# Sheet1.net
KiCad netlist of a schematic drawn in Altium Designer
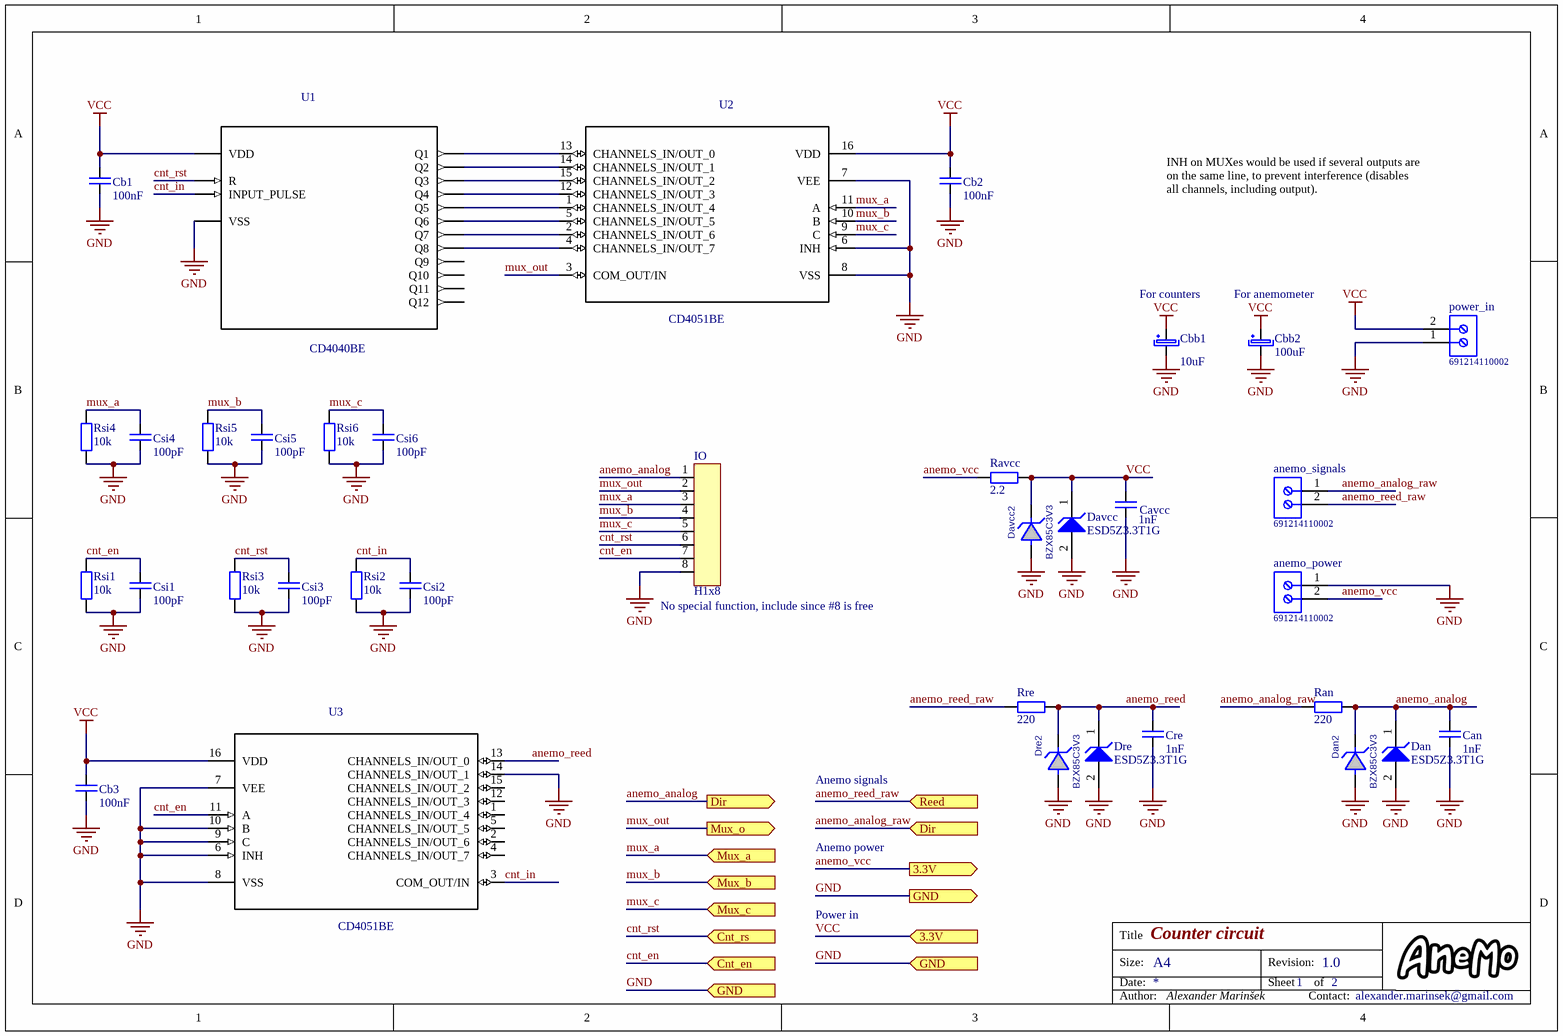
[diagram p0: Sheet1.SchDoc]

(export (version "E")
  (design (tool "Eeschema 10.0.6"))
  (components
    (comp (ref "anemo_power")
      (value "691214110002")
      (footprint "691214110002")
      (description "Serie 2141 - 3.50 mm Horizontal Entry Modular with Rising Cage Clamp WR-TBL, 2 pin")
      (fields (field (name "PUBLISHER") "Wurth Elektronik"))
      (libsource (lib "Altium_TBL_RISING_CAGE_SYSTEM (rev18b)") (part "691214110002"))
    )
    (comp (ref "anemo_signals")
      (value "691214110002")
      (footprint "691214110002")
      (description "Serie 2141 - 3.50 mm Horizontal Entry Modular with Rising Cage Clamp WR-TBL, 2 pin")
      (fields (field (name "PUBLISHER") "Wurth Elektronik"))
      (libsource (lib "Altium_TBL_RISING_CAGE_SYSTEM (rev18b)") (part "691214110002"))
    )
    (comp (ref "Can")
      (value "1nF")
      (footprint "C0805(2012)_M")
      (description "Capacitor")
      (libsource (lib "General") (part "C"))
    )
    (comp (ref "Cavcc")
      (value "1nF")
      (footprint "C0805(2012)_M")
      (description "Capacitor")
      (libsource (lib "General") (part "C"))
    )
    (comp (ref "Cb1")
      (value "100nF")
      (footprint "C0805(2012)_M")
      (description "Capacitor")
      (libsource (lib "General") (part "C"))
    )
    (comp (ref "Cb2")
      (value "100nF")
      (footprint "C0805(2012)_M")
      (description "Capacitor")
      (libsource (lib "General") (part "C"))
    )
    (comp (ref "Cb3")
      (value "100nF")
      (footprint "C0805(2012)_M")
      (description "Capacitor")
      (libsource (lib "General") (part "C"))
    )
    (comp (ref "Cbb1")
      (value "10uF")
      (footprint "C-SMD-ELKO-D")
      (description "Capacitor Polarized")
      (libsource (lib "General") (part "C+"))
    )
    (comp (ref "Cbb2")
      (value "100uF")
      (footprint "C-SMD-ELKO-D")
      (description "Capacitor Polarized")
      (libsource (lib "General") (part "C+"))
    )
    (comp (ref "Cre")
      (value "1nF")
      (footprint "C0805(2012)_M")
      (description "Capacitor")
      (libsource (lib "General") (part "C"))
    )
    (comp (ref "Csi1")
      (value "100pF")
      (footprint "C0805(2012)_M")
      (description "Capacitor")
      (libsource (lib "General") (part "C"))
    )
    (comp (ref "Csi2")
      (value "100pF")
      (footprint "C0805(2012)_M")
      (description "Capacitor")
      (libsource (lib "General") (part "C"))
    )
    (comp (ref "Csi3")
      (value "100pF")
      (footprint "C0805(2012)_M")
      (description "Capacitor")
      (libsource (lib "General") (part "C"))
    )
    (comp (ref "Csi4")
      (value "100pF")
      (footprint "C0805(2012)_M")
      (description "Capacitor")
      (libsource (lib "General") (part "C"))
    )
    (comp (ref "Csi5")
      (value "100pF")
      (footprint "C0805(2012)_M")
      (description "Capacitor")
      (libsource (lib "General") (part "C"))
    )
    (comp (ref "Csi6")
      (value "100pF")
      (footprint "C0805(2012)_M")
      (description "Capacitor")
      (libsource (lib "General") (part "C"))
    )
    (comp (ref "Dan")
      (value "ESD5Z3.3T1G")
      (footprint "ONSC-SOD-523-2-502-01_V")
      (fields (field (name "MANUFACTURER") "On Semiconductor"))
      (libsource (lib "ON Semi ESD Protection Diodes & Arrays") (part "ESD5Z3.3T1G"))
    )
    (comp (ref "Dan2")
      (value "BZX85C3V3")
      (footprint "DO 35 (300MILS)")
      (libsource (lib "SemiCond") (part "BZX85C3V3"))
    )
    (comp (ref "Davcc")
      (value "ESD5Z3.3T1G")
      (footprint "ONSC-SOD-523-2-502-01_V")
      (fields (field (name "MANUFACTURER") "On Semiconductor"))
      (libsource (lib "ON Semi ESD Protection Diodes & Arrays") (part "ESD5Z3.3T1G"))
    )
    (comp (ref "Davcc2")
      (value "BZX85C3V3")
      (footprint "DO 35 (300MILS)")
      (libsource (lib "SemiCond") (part "BZX85C3V3"))
    )
    (comp (ref "Dre")
      (value "ESD5Z3.3T1G")
      (footprint "ONSC-SOD-523-2-502-01_V")
      (fields (field (name "MANUFACTURER") "On Semiconductor"))
      (libsource (lib "ON Semi ESD Protection Diodes & Arrays") (part "ESD5Z3.3T1G"))
    )
    (comp (ref "Dre2")
      (value "BZX85C3V3")
      (footprint "DO 35 (300MILS)")
      (libsource (lib "SemiCond") (part "BZX85C3V3"))
    )
    (comp (ref "IO")
      (value "H1x8")
      (footprint "H1x8")
      (description "Header 1x8 (male)")
      (libsource (lib "Kon_Tipk") (part "H1x8"))
    )
    (comp (ref "power_in")
      (value "691214110002")
      (footprint "691214110002")
      (description "Serie 2141 - 3.50 mm Horizontal Entry Modular with Rising Cage Clamp WR-TBL, 2 pin")
      (fields (field (name "PUBLISHER") "Wurth Elektronik"))
      (libsource (lib "Altium_TBL_RISING_CAGE_SYSTEM (rev18b)") (part "691214110002"))
    )
    (comp (ref "Ran")
      (value "220")
      (footprint "R0805(2012)_M")
      (description "R")
      (libsource (lib "General") (part "R"))
    )
    (comp (ref "Ravcc")
      (value "2.2")
      (footprint "R0805(2012)_M")
      (description "R")
      (libsource (lib "General") (part "R"))
    )
    (comp (ref "Rre")
      (value "220")
      (footprint "R0805(2012)_M")
      (description "R")
      (libsource (lib "General") (part "R"))
    )
    (comp (ref "Rsi1")
      (value "10k")
      (footprint "R0805(2012)_M")
      (description "R")
      (libsource (lib "General") (part "R"))
    )
    (comp (ref "Rsi2")
      (value "10k")
      (footprint "R0805(2012)_M")
      (description "R")
      (libsource (lib "General") (part "R"))
    )
    (comp (ref "Rsi3")
      (value "10k")
      (footprint "R0805(2012)_M")
      (description "R")
      (libsource (lib "General") (part "R"))
    )
    (comp (ref "Rsi4")
      (value "10k")
      (footprint "R0805(2012)_M")
      (description "R")
      (libsource (lib "General") (part "R"))
    )
    (comp (ref "Rsi5")
      (value "10k")
      (footprint "R0805(2012)_M")
      (description "R")
      (libsource (lib "General") (part "R"))
    )
    (comp (ref "Rsi6")
      (value "10k")
      (footprint "R0805(2012)_M")
      (description "R")
      (libsource (lib "General") (part "R"))
    )
    (comp (ref "U1")
      (value "CD4040BE")
      (footprint "*SOIC16")
      (description "Ic Counter Ripple Binary 12 Stage 16dil-300")
      (fields (field (name "MF") "Texas Instruments"))
      (libsource (lib "cd4040") (part "CD4040BE"))
    )
    (comp (ref "U2")
      (value "CD4051BE")
      (footprint "*SOIC16")
      (description "i/c Analg Mx/Dmx 8chan 4051_p_")
      (fields (field (name "MF") "Texas Instruments"))
      (libsource (lib "cd4051") (part "CD4051BE"))
    )
    (comp (ref "U3")
      (value "CD4051BE")
      (footprint "*SOIC16")
      (description "i/c Analg Mx/Dmx 8chan 4051_p_")
      (fields (field (name "MF") "Texas Instruments"))
      (libsource (lib "cd4051") (part "CD4051BE"))
    )
  )
  (nets
    (net (code "1") (name "/anemo_analog") (class "Default")
      (node (ref "Can") (pin "1") (pinfunction "1_1") (pintype "passive"))
      (node (ref "Dan") (pin "1") (pinfunction "K_1") (pintype "passive"))
      (node (ref "Dan2") (pin "K") (pintype "passive"))
      (node (ref "IO") (pin "1") (pinfunction "1_1") (pintype "passive"))
      (node (ref "Ran") (pin "1") (pintype "passive"))
      (node (ref "Ran") (pin "2") (pintype "passive"))
      (node (ref "anemo_signals") (pin "1") (pinfunction "1_1") (pintype "passive"))
    )
    (net (code "2") (name "/anemo_reed") (class "Default")
      (node (ref "Cre") (pin "1") (pinfunction "1_1") (pintype "passive"))
      (node (ref "Dre") (pin "1") (pinfunction "K_1") (pintype "passive"))
      (node (ref "Dre2") (pin "K") (pintype "passive"))
      (node (ref "Rre") (pin "2") (pintype "passive"))
      (node (ref "U3") (pin "13") (pinfunction "CHANNELS_IN/OUT_0_13") (pintype "bidirectional"))
    )
    (net (code "3") (name "/anemo_reed_raw") (class "Default")
      (node (ref "Rre") (pin "1") (pintype "passive"))
      (node (ref "anemo_signals") (pin "2") (pinfunction "2_2") (pintype "passive"))
    )
    (net (code "4") (name "/cnt_en") (class "Default")
      (node (ref "Csi1") (pin "1") (pinfunction "1_1") (pintype "passive"))
      (node (ref "IO") (pin "7") (pinfunction "7_7") (pintype "passive"))
      (node (ref "Rsi1") (pin "1") (pintype "passive"))
      (node (ref "U3") (pin "11") (pinfunction "A_11") (pintype "input"))
    )
    (net (code "5") (name "/cnt_in") (class "Default")
      (node (ref "Csi2") (pin "1") (pinfunction "1_1") (pintype "passive"))
      (node (ref "Rsi2") (pin "1") (pintype "passive"))
      (node (ref "U1") (pin "10") (pinfunction "INPUT_PULSE_10") (pintype "input"))
      (node (ref "U3") (pin "3") (pinfunction "COM_OUT/IN_3") (pintype "bidirectional"))
    )
    (net (code "6") (name "/cnt_rst") (class "Default")
      (node (ref "Csi3") (pin "1") (pinfunction "1_1") (pintype "passive"))
      (node (ref "IO") (pin "6") (pinfunction "6_6") (pintype "passive"))
      (node (ref "Rsi3") (pin "1") (pintype "passive"))
      (node (ref "U1") (pin "11") (pinfunction "R_11") (pintype "input"))
    )
    (net (code "7") (name "/mux_a") (class "Default")
      (node (ref "Csi4") (pin "1") (pinfunction "1_1") (pintype "passive"))
      (node (ref "IO") (pin "3") (pinfunction "3_3") (pintype "passive"))
      (node (ref "Rsi4") (pin "1") (pintype "passive"))
      (node (ref "U2") (pin "11") (pinfunction "A_11") (pintype "input"))
    )
    (net (code "8") (name "/mux_b") (class "Default")
      (node (ref "Csi5") (pin "1") (pinfunction "1_1") (pintype "passive"))
      (node (ref "IO") (pin "4") (pinfunction "4_4") (pintype "passive"))
      (node (ref "Rsi5") (pin "1") (pintype "passive"))
      (node (ref "U2") (pin "10") (pinfunction "B_10") (pintype "input"))
    )
    (net (code "9") (name "/mux_c") (class "Default")
      (node (ref "Csi6") (pin "1") (pinfunction "1_1") (pintype "passive"))
      (node (ref "IO") (pin "5") (pinfunction "5_5") (pintype "passive"))
      (node (ref "Rsi6") (pin "1") (pintype "passive"))
      (node (ref "U2") (pin "9") (pinfunction "C_9") (pintype "input"))
    )
    (net (code "10") (name "/mux_out") (class "Default")
      (node (ref "IO") (pin "2") (pinfunction "2_2") (pintype "passive"))
      (node (ref "U2") (pin "3") (pinfunction "COM_OUT/IN_3") (pintype "bidirectional"))
    )
    (net (code "11") (name "GND") (class "Default")
      (node (ref "Can") (pin "2") (pinfunction "2_2") (pintype "passive"))
      (node (ref "Cavcc") (pin "2") (pinfunction "2_2") (pintype "passive"))
      (node (ref "Cb1") (pin "2") (pinfunction "2_2") (pintype "passive"))
      (node (ref "Cb2") (pin "2") (pinfunction "2_2") (pintype "passive"))
      (node (ref "Cb3") (pin "2") (pinfunction "2_2") (pintype "passive"))
      (node (ref "Cbb1") (pin "2") (pinfunction "2_2") (pintype "passive"))
      (node (ref "Cbb2") (pin "2") (pinfunction "2_2") (pintype "passive"))
      (node (ref "Cre") (pin "2") (pinfunction "2_2") (pintype "passive"))
      (node (ref "Csi1") (pin "2") (pinfunction "2_2") (pintype "passive"))
      (node (ref "Csi2") (pin "2") (pinfunction "2_2") (pintype "passive"))
      (node (ref "Csi3") (pin "2") (pinfunction "2_2") (pintype "passive"))
      (node (ref "Csi4") (pin "2") (pinfunction "2_2") (pintype "passive"))
      (node (ref "Csi5") (pin "2") (pinfunction "2_2") (pintype "passive"))
      (node (ref "Csi6") (pin "2") (pinfunction "2_2") (pintype "passive"))
      (node (ref "Dan") (pin "2") (pinfunction "A_2") (pintype "passive"))
      (node (ref "Dan2") (pin "A") (pintype "passive"))
      (node (ref "Davcc") (pin "2") (pinfunction "A_2") (pintype "passive"))
      (node (ref "Davcc2") (pin "A") (pintype "passive"))
      (node (ref "Dre") (pin "2") (pinfunction "A_2") (pintype "passive"))
      (node (ref "Dre2") (pin "A") (pintype "passive"))
      (node (ref "IO") (pin "8") (pinfunction "8_8") (pintype "passive"))
      (node (ref "Rsi1") (pin "2") (pintype "passive"))
      (node (ref "Rsi2") (pin "2") (pintype "passive"))
      (node (ref "Rsi3") (pin "2") (pintype "passive"))
      (node (ref "Rsi4") (pin "2") (pintype "passive"))
      (node (ref "Rsi5") (pin "2") (pintype "passive"))
      (node (ref "Rsi6") (pin "2") (pintype "passive"))
      (node (ref "U1") (pin "8") (pinfunction "VSS_8") (pintype "passive"))
      (node (ref "U2") (pin "6") (pinfunction "INH_6") (pintype "input"))
      (node (ref "U2") (pin "7") (pinfunction "VEE_7") (pintype "power_in"))
      (node (ref "U2") (pin "8") (pinfunction "VSS_8") (pintype "power_in"))
      (node (ref "U3") (pin "10") (pinfunction "B_10") (pintype "input"))
      (node (ref "U3") (pin "14") (pinfunction "CHANNELS_IN/OUT_1_14") (pintype "bidirectional"))
      (node (ref "U3") (pin "6") (pinfunction "INH_6") (pintype "input"))
      (node (ref "U3") (pin "7") (pinfunction "VEE_7") (pintype "power_in"))
      (node (ref "U3") (pin "8") (pinfunction "VSS_8") (pintype "power_in"))
      (node (ref "U3") (pin "9") (pinfunction "C_9") (pintype "input"))
      (node (ref "anemo_power") (pin "1") (pinfunction "1_1") (pintype "passive"))
      (node (ref "power_in") (pin "1") (pinfunction "1_1") (pintype "passive"))
    )
    (net (code "12") (name "Net-(U1-Q1)") (class "Default")
      (node (ref "U1") (pin "9") (pinfunction "Q1_9") (pintype "output"))
      (node (ref "U2") (pin "13") (pinfunction "CHANNELS_IN/OUT_0_13") (pintype "bidirectional"))
    )
    (net (code "13") (name "Net-(U1-Q2)") (class "Default")
      (node (ref "U1") (pin "7") (pinfunction "Q2_7") (pintype "output"))
      (node (ref "U2") (pin "14") (pinfunction "CHANNELS_IN/OUT_1_14") (pintype "bidirectional"))
    )
    (net (code "14") (name "Net-(U1-Q3)") (class "Default")
      (node (ref "U1") (pin "6") (pinfunction "Q3_6") (pintype "output"))
      (node (ref "U2") (pin "15") (pinfunction "CHANNELS_IN/OUT_2_15") (pintype "bidirectional"))
    )
    (net (code "15") (name "Net-(U1-Q4)") (class "Default")
      (node (ref "U1") (pin "5") (pinfunction "Q4_5") (pintype "output"))
      (node (ref "U2") (pin "12") (pinfunction "CHANNELS_IN/OUT_3_12") (pintype "bidirectional"))
    )
    (net (code "16") (name "Net-(U1-Q5)") (class "Default")
      (node (ref "U1") (pin "3") (pinfunction "Q5_3") (pintype "output"))
      (node (ref "U2") (pin "1") (pinfunction "CHANNELS_IN/OUT_4_1") (pintype "bidirectional"))
    )
    (net (code "17") (name "Net-(U1-Q6)") (class "Default")
      (node (ref "U1") (pin "2") (pinfunction "Q6_2") (pintype "output"))
      (node (ref "U2") (pin "5") (pinfunction "CHANNELS_IN/OUT_5_5") (pintype "bidirectional"))
    )
    (net (code "18") (name "Net-(U1-Q7)") (class "Default")
      (node (ref "U1") (pin "4") (pinfunction "Q7_4") (pintype "output"))
      (node (ref "U2") (pin "2") (pinfunction "CHANNELS_IN/OUT_6_2") (pintype "bidirectional"))
    )
    (net (code "19") (name "Net-(U1-Q8)") (class "Default")
      (node (ref "U1") (pin "13") (pinfunction "Q8_13") (pintype "output"))
      (node (ref "U2") (pin "4") (pinfunction "CHANNELS_IN/OUT_7_4") (pintype "bidirectional"))
    )
    (net (code "20") (name "VCC") (class "Default")
      (node (ref "Cavcc") (pin "1") (pinfunction "1_1") (pintype "passive"))
      (node (ref "Cb1") (pin "1") (pinfunction "1_1") (pintype "passive"))
      (node (ref "Cb2") (pin "1") (pinfunction "1_1") (pintype "passive"))
      (node (ref "Cb3") (pin "1") (pinfunction "1_1") (pintype "passive"))
      (node (ref "Cbb1") (pin "1") (pinfunction "1_1") (pintype "passive"))
      (node (ref "Cbb2") (pin "1") (pinfunction "1_1") (pintype "passive"))
      (node (ref "Davcc") (pin "1") (pinfunction "K_1") (pintype "passive"))
      (node (ref "Davcc2") (pin "K") (pintype "passive"))
      (node (ref "Ravcc") (pin "1") (pintype "passive"))
      (node (ref "Ravcc") (pin "2") (pintype "passive"))
      (node (ref "U1") (pin "16") (pinfunction "VDD_16") (pintype "power_in"))
      (node (ref "U2") (pin "16") (pinfunction "VDD_16") (pintype "power_in"))
      (node (ref "U3") (pin "16") (pinfunction "VDD_16") (pintype "power_in"))
      (node (ref "anemo_power") (pin "2") (pinfunction "2_2") (pintype "passive"))
      (node (ref "power_in") (pin "2") (pinfunction "2_2") (pintype "passive"))
    )
    (net (code "21") (name "unconnected-(U1-Q9-Pad12)") (class "Default")
      (node (ref "U1") (pin "12") (pinfunction "Q9_12") (pintype "output"))
    )
    (net (code "22") (name "unconnected-(U1-Q10-Pad14)") (class "Default")
      (node (ref "U1") (pin "14") (pinfunction "Q10_14") (pintype "output"))
    )
    (net (code "23") (name "unconnected-(U1-Q11-Pad15)") (class "Default")
      (node (ref "U1") (pin "15") (pinfunction "Q11_15") (pintype "output"))
    )
    (net (code "24") (name "unconnected-(U1-Q12-Pad1)") (class "Default")
      (node (ref "U1") (pin "1") (pinfunction "Q12_1") (pintype "output"))
    )
    (net (code "25") (name "unconnected-(U3-CHANNELS_IN{slash}OUT_2-Pad15)") (class "Default")
      (node (ref "U3") (pin "15") (pinfunction "CHANNELS_IN/OUT_2_15") (pintype "bidirectional"))
    )
    (net (code "26") (name "unconnected-(U3-CHANNELS_IN{slash}OUT_3-Pad12)") (class "Default")
      (node (ref "U3") (pin "12") (pinfunction "CHANNELS_IN/OUT_3_12") (pintype "bidirectional"))
    )
    (net (code "27") (name "unconnected-(U3-CHANNELS_IN{slash}OUT_4-Pad1)") (class "Default")
      (node (ref "U3") (pin "1") (pinfunction "CHANNELS_IN/OUT_4_1") (pintype "bidirectional"))
    )
    (net (code "28") (name "unconnected-(U3-CHANNELS_IN{slash}OUT_5-Pad5)") (class "Default")
      (node (ref "U3") (pin "5") (pinfunction "CHANNELS_IN/OUT_5_5") (pintype "bidirectional"))
    )
    (net (code "29") (name "unconnected-(U3-CHANNELS_IN{slash}OUT_6-Pad2)") (class "Default")
      (node (ref "U3") (pin "2") (pinfunction "CHANNELS_IN/OUT_6_2") (pintype "bidirectional"))
    )
    (net (code "30") (name "unconnected-(U3-CHANNELS_IN{slash}OUT_7-Pad4)") (class "Default")
      (node (ref "U3") (pin "4") (pinfunction "CHANNELS_IN/OUT_7_4") (pintype "bidirectional"))
    )
  )
)
